# RTL8367N.net
KiCad netlist of a schematic drawn in Altium Designer
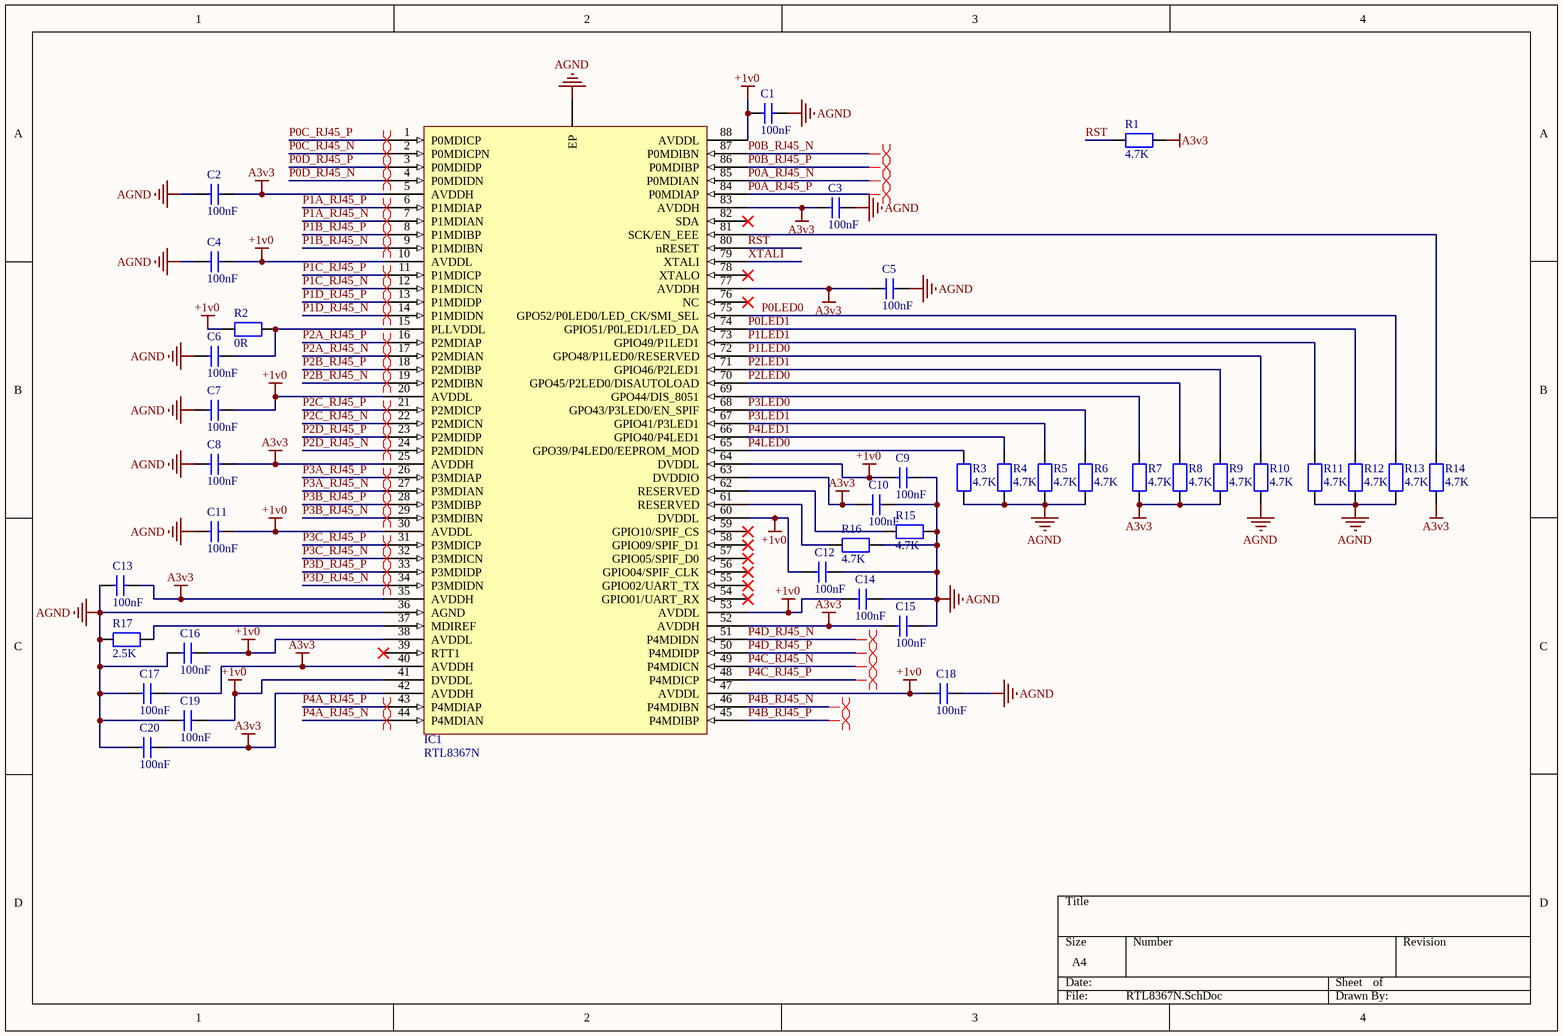
[diagram p0: RTL8367N.SchDoc]

(export (version "E")
  (design (tool "Eeschema 10.0.6"))
  (components
    (comp (ref "C1")
      (value "100nF")
      (footprint "C-0603")
      (description "C-0603")
      (libsource (lib "Switch_Schlib") (part "C-0603"))
    )
    (comp (ref "C2")
      (value "100nF")
      (footprint "C-0603")
      (description "C-0603")
      (libsource (lib "Switch_Schlib") (part "C-0603"))
    )
    (comp (ref "C3")
      (value "100nF")
      (footprint "C-0603")
      (description "C-0603")
      (libsource (lib "Switch_Schlib") (part "C-0603"))
    )
    (comp (ref "C4")
      (value "100nF")
      (footprint "C-0603")
      (description "C-0603")
      (libsource (lib "Switch_Schlib") (part "C-0603"))
    )
    (comp (ref "C5")
      (value "100nF")
      (footprint "C-0603")
      (description "C-0603")
      (libsource (lib "Switch_Schlib") (part "C-0603"))
    )
    (comp (ref "C6")
      (value "100nF")
      (footprint "C-0603")
      (description "C-0603")
      (libsource (lib "Switch_Schlib") (part "C-0603"))
    )
    (comp (ref "C7")
      (value "100nF")
      (footprint "C-0603")
      (description "C-0603")
      (libsource (lib "Switch_Schlib") (part "C-0603"))
    )
    (comp (ref "C8")
      (value "100nF")
      (footprint "C-0603")
      (description "C-0603")
      (libsource (lib "Switch_Schlib") (part "C-0603"))
    )
    (comp (ref "C9")
      (value "100nF")
      (footprint "C-0603")
      (description "C-0603")
      (libsource (lib "Switch_Schlib") (part "C-0603"))
    )
    (comp (ref "C10")
      (value "100nF")
      (footprint "C-0603")
      (description "C-0603")
      (libsource (lib "Switch_Schlib") (part "C-0603"))
    )
    (comp (ref "C11")
      (value "100nF")
      (footprint "C-0603")
      (description "C-0603")
      (libsource (lib "Switch_Schlib") (part "C-0603"))
    )
    (comp (ref "C12")
      (value "100nF")
      (footprint "C-0603")
      (description "C-0603")
      (libsource (lib "Switch_Schlib") (part "C-0603"))
    )
    (comp (ref "C13")
      (value "100nF")
      (footprint "C-0603")
      (description "C-0603")
      (libsource (lib "Switch_Schlib") (part "C-0603"))
    )
    (comp (ref "C14")
      (value "100nF")
      (footprint "C-0603")
      (description "C-0603")
      (libsource (lib "Switch_Schlib") (part "C-0603"))
    )
    (comp (ref "C15")
      (value "100nF")
      (footprint "C-0603")
      (description "C-0603")
      (libsource (lib "Switch_Schlib") (part "C-0603"))
    )
    (comp (ref "C16")
      (value "100nF")
      (footprint "C-0603")
      (description "C-0603")
      (libsource (lib "Switch_Schlib") (part "C-0603"))
    )
    (comp (ref "C17")
      (value "100nF")
      (footprint "C-0603")
      (description "C-0603")
      (libsource (lib "Switch_Schlib") (part "C-0603"))
    )
    (comp (ref "C18")
      (value "100nF")
      (footprint "C-0603")
      (description "C-0603")
      (libsource (lib "Switch_Schlib") (part "C-0603"))
    )
    (comp (ref "C19")
      (value "100nF")
      (footprint "C-0603")
      (description "C-0603")
      (libsource (lib "Switch_Schlib") (part "C-0603"))
    )
    (comp (ref "C20")
      (value "100nF")
      (footprint "C-0603")
      (description "C-0603")
      (libsource (lib "Switch_Schlib") (part "C-0603"))
    )
    (comp (ref "IC1")
      (value "RTL8367N")
      (footprint "QFN40P1000X1000X90_HS-89M")
      (description "RTL8367N-VB-CG")
      (libsource (lib "Switch_Schlib") (part "RTL8367N"))
    )
    (comp (ref "R1")
      (value "4.7K")
      (footprint "RESMELF3515L")
      (description "CSR-0204")
      (libsource (lib "Switch_Schlib") (part "CSR-0204"))
    )
    (comp (ref "R2")
      (value "0R")
      (footprint "RESMELF3515L")
      (description "CSR-0204")
      (libsource (lib "Switch_Schlib") (part "CSR-0204"))
    )
    (comp (ref "R3")
      (value "4.7K")
      (footprint "RESMELF3515L")
      (description "CSR-0204")
      (libsource (lib "Switch_Schlib") (part "CSR-0204"))
    )
    (comp (ref "R4")
      (value "4.7K")
      (footprint "RESMELF3515L")
      (description "CSR-0204")
      (libsource (lib "Switch_Schlib") (part "CSR-0204"))
    )
    (comp (ref "R5")
      (value "4.7K")
      (footprint "RESMELF3515L")
      (description "CSR-0204")
      (libsource (lib "Switch_Schlib") (part "CSR-0204"))
    )
    (comp (ref "R6")
      (value "4.7K")
      (footprint "RESMELF3515L")
      (description "CSR-0204")
      (libsource (lib "Switch_Schlib") (part "CSR-0204"))
    )
    (comp (ref "R7")
      (value "4.7K")
      (footprint "RESMELF3515L")
      (description "CSR-0204")
      (libsource (lib "Switch_Schlib") (part "CSR-0204"))
    )
    (comp (ref "R8")
      (value "4.7K")
      (footprint "RESMELF3515L")
      (description "CSR-0204")
      (libsource (lib "Switch_Schlib") (part "CSR-0204"))
    )
    (comp (ref "R9")
      (value "4.7K")
      (footprint "RESMELF3515L")
      (description "CSR-0204")
      (libsource (lib "Switch_Schlib") (part "CSR-0204"))
    )
    (comp (ref "R10")
      (value "4.7K")
      (footprint "RESMELF3515L")
      (description "CSR-0204")
      (libsource (lib "Switch_Schlib") (part "CSR-0204"))
    )
    (comp (ref "R11")
      (value "4.7K")
      (footprint "RESMELF3515L")
      (description "CSR-0204")
      (libsource (lib "Switch_Schlib") (part "CSR-0204"))
    )
    (comp (ref "R12")
      (value "4.7K")
      (footprint "RESMELF3515L")
      (description "CSR-0204")
      (libsource (lib "Switch_Schlib") (part "CSR-0204"))
    )
    (comp (ref "R13")
      (value "4.7K")
      (footprint "RESMELF3515L")
      (description "CSR-0204")
      (libsource (lib "Switch_Schlib") (part "CSR-0204"))
    )
    (comp (ref "R14")
      (value "4.7K")
      (footprint "RESMELF3515L")
      (description "CSR-0204")
      (libsource (lib "Switch_Schlib") (part "CSR-0204"))
    )
    (comp (ref "R15")
      (value "4.7K")
      (footprint "RESMELF3515L")
      (description "CSR-0204")
      (libsource (lib "Switch_Schlib") (part "CSR-0204"))
    )
    (comp (ref "R16")
      (value "4.7K")
      (footprint "RESMELF3515L")
      (description "CSR-0204")
      (libsource (lib "Switch_Schlib") (part "CSR-0204"))
    )
    (comp (ref "R17")
      (value "2.5K")
      (footprint "RESMELF3515L")
      (description "CSR-0204")
      (libsource (lib "Switch_Schlib") (part "CSR-0204"))
    )
  )
  (nets
    (net (code "1") (name "+1v0") (class "Default")
      (node (ref "C1") (pin "1") (pintype "passive"))
      (node (ref "C11") (pin "2") (pintype "passive"))
      (node (ref "C12") (pin "1") (pintype "passive"))
      (node (ref "C14") (pin "1") (pintype "passive"))
      (node (ref "C16") (pin "2") (pintype "passive"))
      (node (ref "C18") (pin "1") (pintype "passive"))
      (node (ref "C19") (pin "2") (pintype "passive"))
      (node (ref "C4") (pin "2") (pintype "passive"))
      (node (ref "C7") (pin "2") (pintype "passive"))
      (node (ref "C9") (pin "1") (pintype "passive"))
      (node (ref "IC1") (pin "10") (pinfunction "AVDDL_10") (pintype "power_in"))
      (node (ref "IC1") (pin "20") (pinfunction "AVDDL_20") (pintype "power_in"))
      (node (ref "IC1") (pin "30") (pinfunction "AVDDL_30") (pintype "power_in"))
      (node (ref "IC1") (pin "38") (pinfunction "AVDDL_38") (pintype "power_in"))
      (node (ref "IC1") (pin "41") (pinfunction "DVDDL_41") (pintype "power_in"))
      (node (ref "IC1") (pin "47") (pinfunction "AVDDL_47") (pintype "power_in"))
      (node (ref "IC1") (pin "53") (pinfunction "AVDDL_53") (pintype "power_in"))
      (node (ref "IC1") (pin "60") (pinfunction "DVDDL_60") (pintype "input"))
      (node (ref "IC1") (pin "64") (pinfunction "DVDDL_64") (pintype "input"))
      (node (ref "IC1") (pin "88") (pinfunction "AVDDL_88") (pintype "power_in"))
      (node (ref "R2") (pin "1") (pintype "passive"))
    )
    (net (code "2") (name "/P0A_RJ45_N") (class "Default")
      (node (ref "IC1") (pin "85") (pinfunction "P0MDIAN_85") (pintype "input"))
    )
    (net (code "3") (name "/P0A_RJ45_P") (class "Default")
      (node (ref "IC1") (pin "84") (pinfunction "P0MDIAP_84") (pintype "input"))
    )
    (net (code "4") (name "/P0B_RJ45_N") (class "Default")
      (node (ref "IC1") (pin "87") (pinfunction "P0MDIBN_87") (pintype "input"))
    )
    (net (code "5") (name "/P0B_RJ45_P") (class "Default")
      (node (ref "IC1") (pin "86") (pinfunction "P0MDIBP_86") (pintype "input"))
    )
    (net (code "6") (name "/P0C_RJ45_N") (class "Default")
      (node (ref "IC1") (pin "2") (pinfunction "P0MDICPN_2") (pintype "input"))
    )
    (net (code "7") (name "/P0C_RJ45_P") (class "Default")
      (node (ref "IC1") (pin "1") (pinfunction "P0MDICP_1") (pintype "input"))
    )
    (net (code "8") (name "/P0D_RJ45_N") (class "Default")
      (node (ref "IC1") (pin "4") (pinfunction "P0MDIDN_4") (pintype "input"))
    )
    (net (code "9") (name "/P0D_RJ45_P") (class "Default")
      (node (ref "IC1") (pin "3") (pinfunction "P0MDIDP_3") (pintype "input"))
    )
    (net (code "10") (name "/P0LED0") (class "Default")
      (node (ref "IC1") (pin "75") (pinfunction "GPO52/P0LED0/LED_CK/SMI_SEL_75") (pintype "input"))
      (node (ref "R13") (pin "2") (pintype "passive"))
    )
    (net (code "11") (name "/P0LED1") (class "Default")
      (node (ref "IC1") (pin "74") (pinfunction "GPIO51/P0LED1/LED_DA_74") (pintype "input"))
      (node (ref "R12") (pin "2") (pintype "passive"))
    )
    (net (code "12") (name "/P1A_RJ45_N") (class "Default")
      (node (ref "IC1") (pin "7") (pinfunction "P1MDIAN_7") (pintype "input"))
    )
    (net (code "13") (name "/P1A_RJ45_P") (class "Default")
      (node (ref "IC1") (pin "6") (pinfunction "P1MDIAP_6") (pintype "input"))
    )
    (net (code "14") (name "/P1B_RJ45_N") (class "Default")
      (node (ref "IC1") (pin "9") (pinfunction "P1MDIBN_9") (pintype "input"))
    )
    (net (code "15") (name "/P1B_RJ45_P") (class "Default")
      (node (ref "IC1") (pin "8") (pinfunction "P1MDIBP_8") (pintype "input"))
    )
    (net (code "16") (name "/P1C_RJ45_N") (class "Default")
      (node (ref "IC1") (pin "12") (pinfunction "P1MDICN_12") (pintype "input"))
    )
    (net (code "17") (name "/P1C_RJ45_P") (class "Default")
      (node (ref "IC1") (pin "11") (pinfunction "P1MDICP_11") (pintype "input"))
    )
    (net (code "18") (name "/P1D_RJ45_N") (class "Default")
      (node (ref "IC1") (pin "14") (pinfunction "P1MDIDN_14") (pintype "input"))
    )
    (net (code "19") (name "/P1D_RJ45_P") (class "Default")
      (node (ref "IC1") (pin "13") (pinfunction "P1MDIDP_13") (pintype "input"))
    )
    (net (code "20") (name "/P1LED0") (class "Default")
      (node (ref "IC1") (pin "72") (pinfunction "GPO48/P1LED0/RESERVED_72") (pintype "input"))
      (node (ref "R10") (pin "2") (pintype "passive"))
    )
    (net (code "21") (name "/P1LED1") (class "Default")
      (node (ref "IC1") (pin "73") (pinfunction "GPIO49/P1LED1_73") (pintype "input"))
      (node (ref "R11") (pin "2") (pintype "passive"))
    )
    (net (code "22") (name "/P2A_RJ45_N") (class "Default")
      (node (ref "IC1") (pin "17") (pinfunction "P2MDIAN_17") (pintype "input"))
    )
    (net (code "23") (name "/P2A_RJ45_P") (class "Default")
      (node (ref "IC1") (pin "16") (pinfunction "P2MDIAP_16") (pintype "input"))
    )
    (net (code "24") (name "/P2B_RJ45_N") (class "Default")
      (node (ref "IC1") (pin "19") (pinfunction "P2MDIBN_19") (pintype "input"))
    )
    (net (code "25") (name "/P2B_RJ45_P") (class "Default")
      (node (ref "IC1") (pin "18") (pinfunction "P2MDIBP_18") (pintype "input"))
    )
    (net (code "26") (name "/P2C_RJ45_N") (class "Default")
      (node (ref "IC1") (pin "22") (pinfunction "P2MDICN_22") (pintype "input"))
    )
    (net (code "27") (name "/P2C_RJ45_P") (class "Default")
      (node (ref "IC1") (pin "21") (pinfunction "P2MDICP_21") (pintype "input"))
    )
    (net (code "28") (name "/P2D_RJ45_N") (class "Default")
      (node (ref "IC1") (pin "24") (pinfunction "P2MDIDN_24") (pintype "input"))
    )
    (net (code "29") (name "/P2D_RJ45_P") (class "Default")
      (node (ref "IC1") (pin "23") (pinfunction "P2MDIDP_23") (pintype "input"))
    )
    (net (code "30") (name "/P2LED0") (class "Default")
      (node (ref "IC1") (pin "70") (pinfunction "GPO45/P2LED0/DISAUTOLOAD_70") (pintype "input"))
      (node (ref "R8") (pin "2") (pintype "passive"))
    )
    (net (code "31") (name "/P2LED1") (class "Default")
      (node (ref "IC1") (pin "71") (pinfunction "GPIO46/P2LED1_71") (pintype "input"))
      (node (ref "R9") (pin "2") (pintype "passive"))
    )
    (net (code "32") (name "/P3A_RJ45_N") (class "Default")
      (node (ref "IC1") (pin "27") (pinfunction "P3MDIAN_27") (pintype "input"))
    )
    (net (code "33") (name "/P3A_RJ45_P") (class "Default")
      (node (ref "IC1") (pin "26") (pinfunction "P3MDIAP_26") (pintype "input"))
    )
    (net (code "34") (name "/P3B_RJ45_N") (class "Default")
      (node (ref "IC1") (pin "29") (pinfunction "P3MDIBN_29") (pintype "input"))
    )
    (net (code "35") (name "/P3B_RJ45_P") (class "Default")
      (node (ref "IC1") (pin "28") (pinfunction "P3MDIBP_28") (pintype "input"))
    )
    (net (code "36") (name "/P3C_RJ45_N") (class "Default")
      (node (ref "IC1") (pin "32") (pinfunction "P3MDICN_32") (pintype "input"))
    )
    (net (code "37") (name "/P3C_RJ45_P") (class "Default")
      (node (ref "IC1") (pin "31") (pinfunction "P3MDICP_31") (pintype "input"))
    )
    (net (code "38") (name "/P3D_RJ45_N") (class "Default")
      (node (ref "IC1") (pin "34") (pinfunction "P3MDIDN_34") (pintype "input"))
    )
    (net (code "39") (name "/P3D_RJ45_P") (class "Default")
      (node (ref "IC1") (pin "33") (pinfunction "P3MDIDP_33") (pintype "input"))
    )
    (net (code "40") (name "/P3LED0") (class "Default")
      (node (ref "IC1") (pin "68") (pinfunction "GPO43/P3LED0/EN_SPIF_68") (pintype "input"))
      (node (ref "R6") (pin "2") (pintype "passive"))
    )
    (net (code "41") (name "/P3LED1") (class "Default")
      (node (ref "IC1") (pin "67") (pinfunction "GPIO41/P3LED1_67") (pintype "input"))
      (node (ref "R5") (pin "2") (pintype "passive"))
    )
    (net (code "42") (name "/P4A_RJ45_N") (class "Default")
      (node (ref "IC1") (pin "44") (pinfunction "P4MDIAN_44") (pintype "input"))
    )
    (net (code "43") (name "/P4A_RJ45_P") (class "Default")
      (node (ref "IC1") (pin "43") (pinfunction "P4MDIAP_43") (pintype "input"))
    )
    (net (code "44") (name "/P4B_RJ45_N") (class "Default")
      (node (ref "IC1") (pin "46") (pinfunction "P4MDIBN_46") (pintype "input"))
    )
    (net (code "45") (name "/P4B_RJ45_P") (class "Default")
      (node (ref "IC1") (pin "45") (pinfunction "P4MDIBP_45") (pintype "input"))
    )
    (net (code "46") (name "/P4C_RJ45_N") (class "Default")
      (node (ref "IC1") (pin "49") (pinfunction "P4MDICN_49") (pintype "input"))
    )
    (net (code "47") (name "/P4C_RJ45_P") (class "Default")
      (node (ref "IC1") (pin "48") (pinfunction "P4MDICP_48") (pintype "input"))
    )
    (net (code "48") (name "/P4D_RJ45_N") (class "Default")
      (node (ref "IC1") (pin "51") (pinfunction "P4MDIDN_51") (pintype "input"))
    )
    (net (code "49") (name "/P4D_RJ45_P") (class "Default")
      (node (ref "IC1") (pin "50") (pinfunction "P4MDIDP_50") (pintype "input"))
    )
    (net (code "50") (name "/P4LED0") (class "Default")
      (node (ref "IC1") (pin "65") (pinfunction "GPO39/P4LED0/EEPROM_MOD_65") (pintype "input"))
      (node (ref "R3") (pin "2") (pintype "passive"))
    )
    (net (code "51") (name "/P4LED1") (class "Default")
      (node (ref "IC1") (pin "66") (pinfunction "GPIO40/P4LED1_66") (pintype "input"))
      (node (ref "R4") (pin "2") (pintype "passive"))
    )
    (net (code "52") (name "/RST") (class "Default")
      (node (ref "IC1") (pin "80") (pinfunction "nRESET_80") (pintype "input"))
      (node (ref "R1") (pin "1") (pintype "passive"))
    )
    (net (code "53") (name "/XTALI") (class "Default")
      (node (ref "IC1") (pin "79") (pinfunction "XTALI_79") (pintype "input"))
    )
    (net (code "54") (name "A3v3") (class "Default")
      (node (ref "C10") (pin "1") (pintype "passive"))
      (node (ref "C13") (pin "2") (pintype "passive"))
      (node (ref "C15") (pin "1") (pintype "passive"))
      (node (ref "C17") (pin "2") (pintype "passive"))
      (node (ref "C2") (pin "2") (pintype "passive"))
      (node (ref "C20") (pin "2") (pintype "passive"))
      (node (ref "C3") (pin "1") (pintype "passive"))
      (node (ref "C5") (pin "1") (pintype "passive"))
      (node (ref "C8") (pin "2") (pintype "passive"))
      (node (ref "IC1") (pin "25") (pinfunction "AVDDH_25") (pintype "power_in"))
      (node (ref "IC1") (pin "35") (pinfunction "AVDDH_35") (pintype "power_in"))
      (node (ref "IC1") (pin "40") (pinfunction "AVDDH_40") (pintype "power_in"))
      (node (ref "IC1") (pin "42") (pinfunction "AVDDH_42") (pintype "power_in"))
      (node (ref "IC1") (pin "5") (pinfunction "AVDDH_5") (pintype "power_in"))
      (node (ref "IC1") (pin "52") (pinfunction "AVDDH_52") (pintype "power_in"))
      (node (ref "IC1") (pin "63") (pinfunction "DVDDIO_63") (pintype "input"))
      (node (ref "IC1") (pin "77") (pinfunction "AVDDH_77") (pintype "power_in"))
      (node (ref "IC1") (pin "83") (pinfunction "AVDDH_83") (pintype "power_in"))
      (node (ref "R1") (pin "2") (pintype "passive"))
      (node (ref "R14") (pin "1") (pintype "passive"))
      (node (ref "R7") (pin "1") (pintype "passive"))
      (node (ref "R8") (pin "1") (pintype "passive"))
      (node (ref "R9") (pin "1") (pintype "passive"))
    )
    (net (code "55") (name "AGND") (class "Default")
      (node (ref "C1") (pin "2") (pintype "passive"))
      (node (ref "C10") (pin "2") (pintype "passive"))
      (node (ref "C11") (pin "1") (pintype "passive"))
      (node (ref "C12") (pin "2") (pintype "passive"))
      (node (ref "C13") (pin "1") (pintype "passive"))
      (node (ref "C14") (pin "2") (pintype "passive"))
      (node (ref "C15") (pin "2") (pintype "passive"))
      (node (ref "C16") (pin "1") (pintype "passive"))
      (node (ref "C17") (pin "1") (pintype "passive"))
      (node (ref "C18") (pin "2") (pintype "passive"))
      (node (ref "C19") (pin "1") (pintype "passive"))
      (node (ref "C2") (pin "1") (pintype "passive"))
      (node (ref "C20") (pin "1") (pintype "passive"))
      (node (ref "C3") (pin "2") (pintype "passive"))
      (node (ref "C4") (pin "1") (pintype "passive"))
      (node (ref "C5") (pin "2") (pintype "passive"))
      (node (ref "C6") (pin "1") (pintype "passive"))
      (node (ref "C7") (pin "1") (pintype "passive"))
      (node (ref "C8") (pin "1") (pintype "passive"))
      (node (ref "C9") (pin "2") (pintype "passive"))
      (node (ref "IC1") (pin "36") (pinfunction "AGND_36") (pintype "input"))
      (node (ref "IC1") (pin "89") (pinfunction "EP_89") (pintype "passive"))
      (node (ref "R10") (pin "1") (pintype "passive"))
      (node (ref "R11") (pin "1") (pintype "passive"))
      (node (ref "R12") (pin "1") (pintype "passive"))
      (node (ref "R13") (pin "1") (pintype "passive"))
      (node (ref "R15") (pin "2") (pintype "passive"))
      (node (ref "R16") (pin "2") (pintype "passive"))
      (node (ref "R17") (pin "1") (pintype "passive"))
      (node (ref "R3") (pin "1") (pintype "passive"))
      (node (ref "R4") (pin "1") (pintype "passive"))
      (node (ref "R5") (pin "1") (pintype "passive"))
      (node (ref "R6") (pin "1") (pintype "passive"))
    )
    (net (code "56") (name "Net-(IC1-GPO44{slash}DIS_8051)") (class "Default")
      (node (ref "IC1") (pin "69") (pinfunction "GPO44/DIS_8051_69") (pintype "input"))
      (node (ref "R7") (pin "2") (pintype "passive"))
    )
    (net (code "57") (name "Net-(IC1-MDIREF)") (class "Default")
      (node (ref "IC1") (pin "37") (pinfunction "MDIREF_37") (pintype "input"))
      (node (ref "R17") (pin "2") (pintype "passive"))
    )
    (net (code "58") (name "Net-(IC1-PLLVDDL)") (class "Default")
      (node (ref "C6") (pin "2") (pintype "passive"))
      (node (ref "IC1") (pin "15") (pinfunction "PLLVDDL_15") (pintype "power_in"))
      (node (ref "R2") (pin "2") (pintype "passive"))
    )
    (net (code "59") (name "Net-(IC1-RESERVED-Pad61)") (class "Default")
      (node (ref "IC1") (pin "61") (pinfunction "RESERVED_61") (pintype "input"))
      (node (ref "R16") (pin "1") (pintype "passive"))
    )
    (net (code "60") (name "Net-(IC1-RESERVED-Pad62)") (class "Default")
      (node (ref "IC1") (pin "62") (pinfunction "RESERVED_62") (pintype "input"))
      (node (ref "R15") (pin "1") (pintype "passive"))
    )
    (net (code "61") (name "Net-(IC1-SCK{slash}EN_EEE)") (class "Default")
      (node (ref "IC1") (pin "81") (pinfunction "SCK/EN_EEE_81") (pintype "input"))
      (node (ref "R14") (pin "2") (pintype "passive"))
    )
    (net (code "62") (name "unconnected-(IC1-GPIO01{slash}UART_RX-Pad54)") (class "Default")
      (node (ref "IC1") (pin "54") (pinfunction "GPIO01/UART_RX_54") (pintype "input+no_connect"))
    )
    (net (code "63") (name "unconnected-(IC1-GPIO02{slash}UART_TX-Pad55)") (class "Default")
      (node (ref "IC1") (pin "55") (pinfunction "GPIO02/UART_TX_55") (pintype "input+no_connect"))
    )
    (net (code "64") (name "unconnected-(IC1-GPIO04{slash}SPIF_CLK-Pad56)") (class "Default")
      (node (ref "IC1") (pin "56") (pinfunction "GPIO04/SPIF_CLK_56") (pintype "input+no_connect"))
    )
    (net (code "65") (name "unconnected-(IC1-GPIO05{slash}SPIF_D0-Pad57)") (class "Default")
      (node (ref "IC1") (pin "57") (pinfunction "GPIO05/SPIF_D0_57") (pintype "input+no_connect"))
    )
    (net (code "66") (name "unconnected-(IC1-GPIO09{slash}SPIF_D1-Pad58)") (class "Default")
      (node (ref "IC1") (pin "58") (pinfunction "GPIO09/SPIF_D1_58") (pintype "input+no_connect"))
    )
    (net (code "67") (name "unconnected-(IC1-GPIO10{slash}SPIF_CS-Pad59)") (class "Default")
      (node (ref "IC1") (pin "59") (pinfunction "GPIO10/SPIF_CS_59") (pintype "input+no_connect"))
    )
    (net (code "68") (name "unconnected-(IC1-NC-Pad76)") (class "Default")
      (node (ref "IC1") (pin "76") (pinfunction "NC_76") (pintype "input+no_connect"))
    )
    (net (code "69") (name "unconnected-(IC1-RTT1-Pad39)") (class "Default")
      (node (ref "IC1") (pin "39") (pinfunction "RTT1_39") (pintype "input+no_connect"))
    )
    (net (code "70") (name "unconnected-(IC1-SDA-Pad82)") (class "Default")
      (node (ref "IC1") (pin "82") (pinfunction "SDA_82") (pintype "input+no_connect"))
    )
    (net (code "71") (name "unconnected-(IC1-XTALO-Pad78)") (class "Default")
      (node (ref "IC1") (pin "78") (pinfunction "XTALO_78") (pintype "input+no_connect"))
    )
  )
)
